# PCB.net
KiCad netlist of a schematic drawn in EAGLE
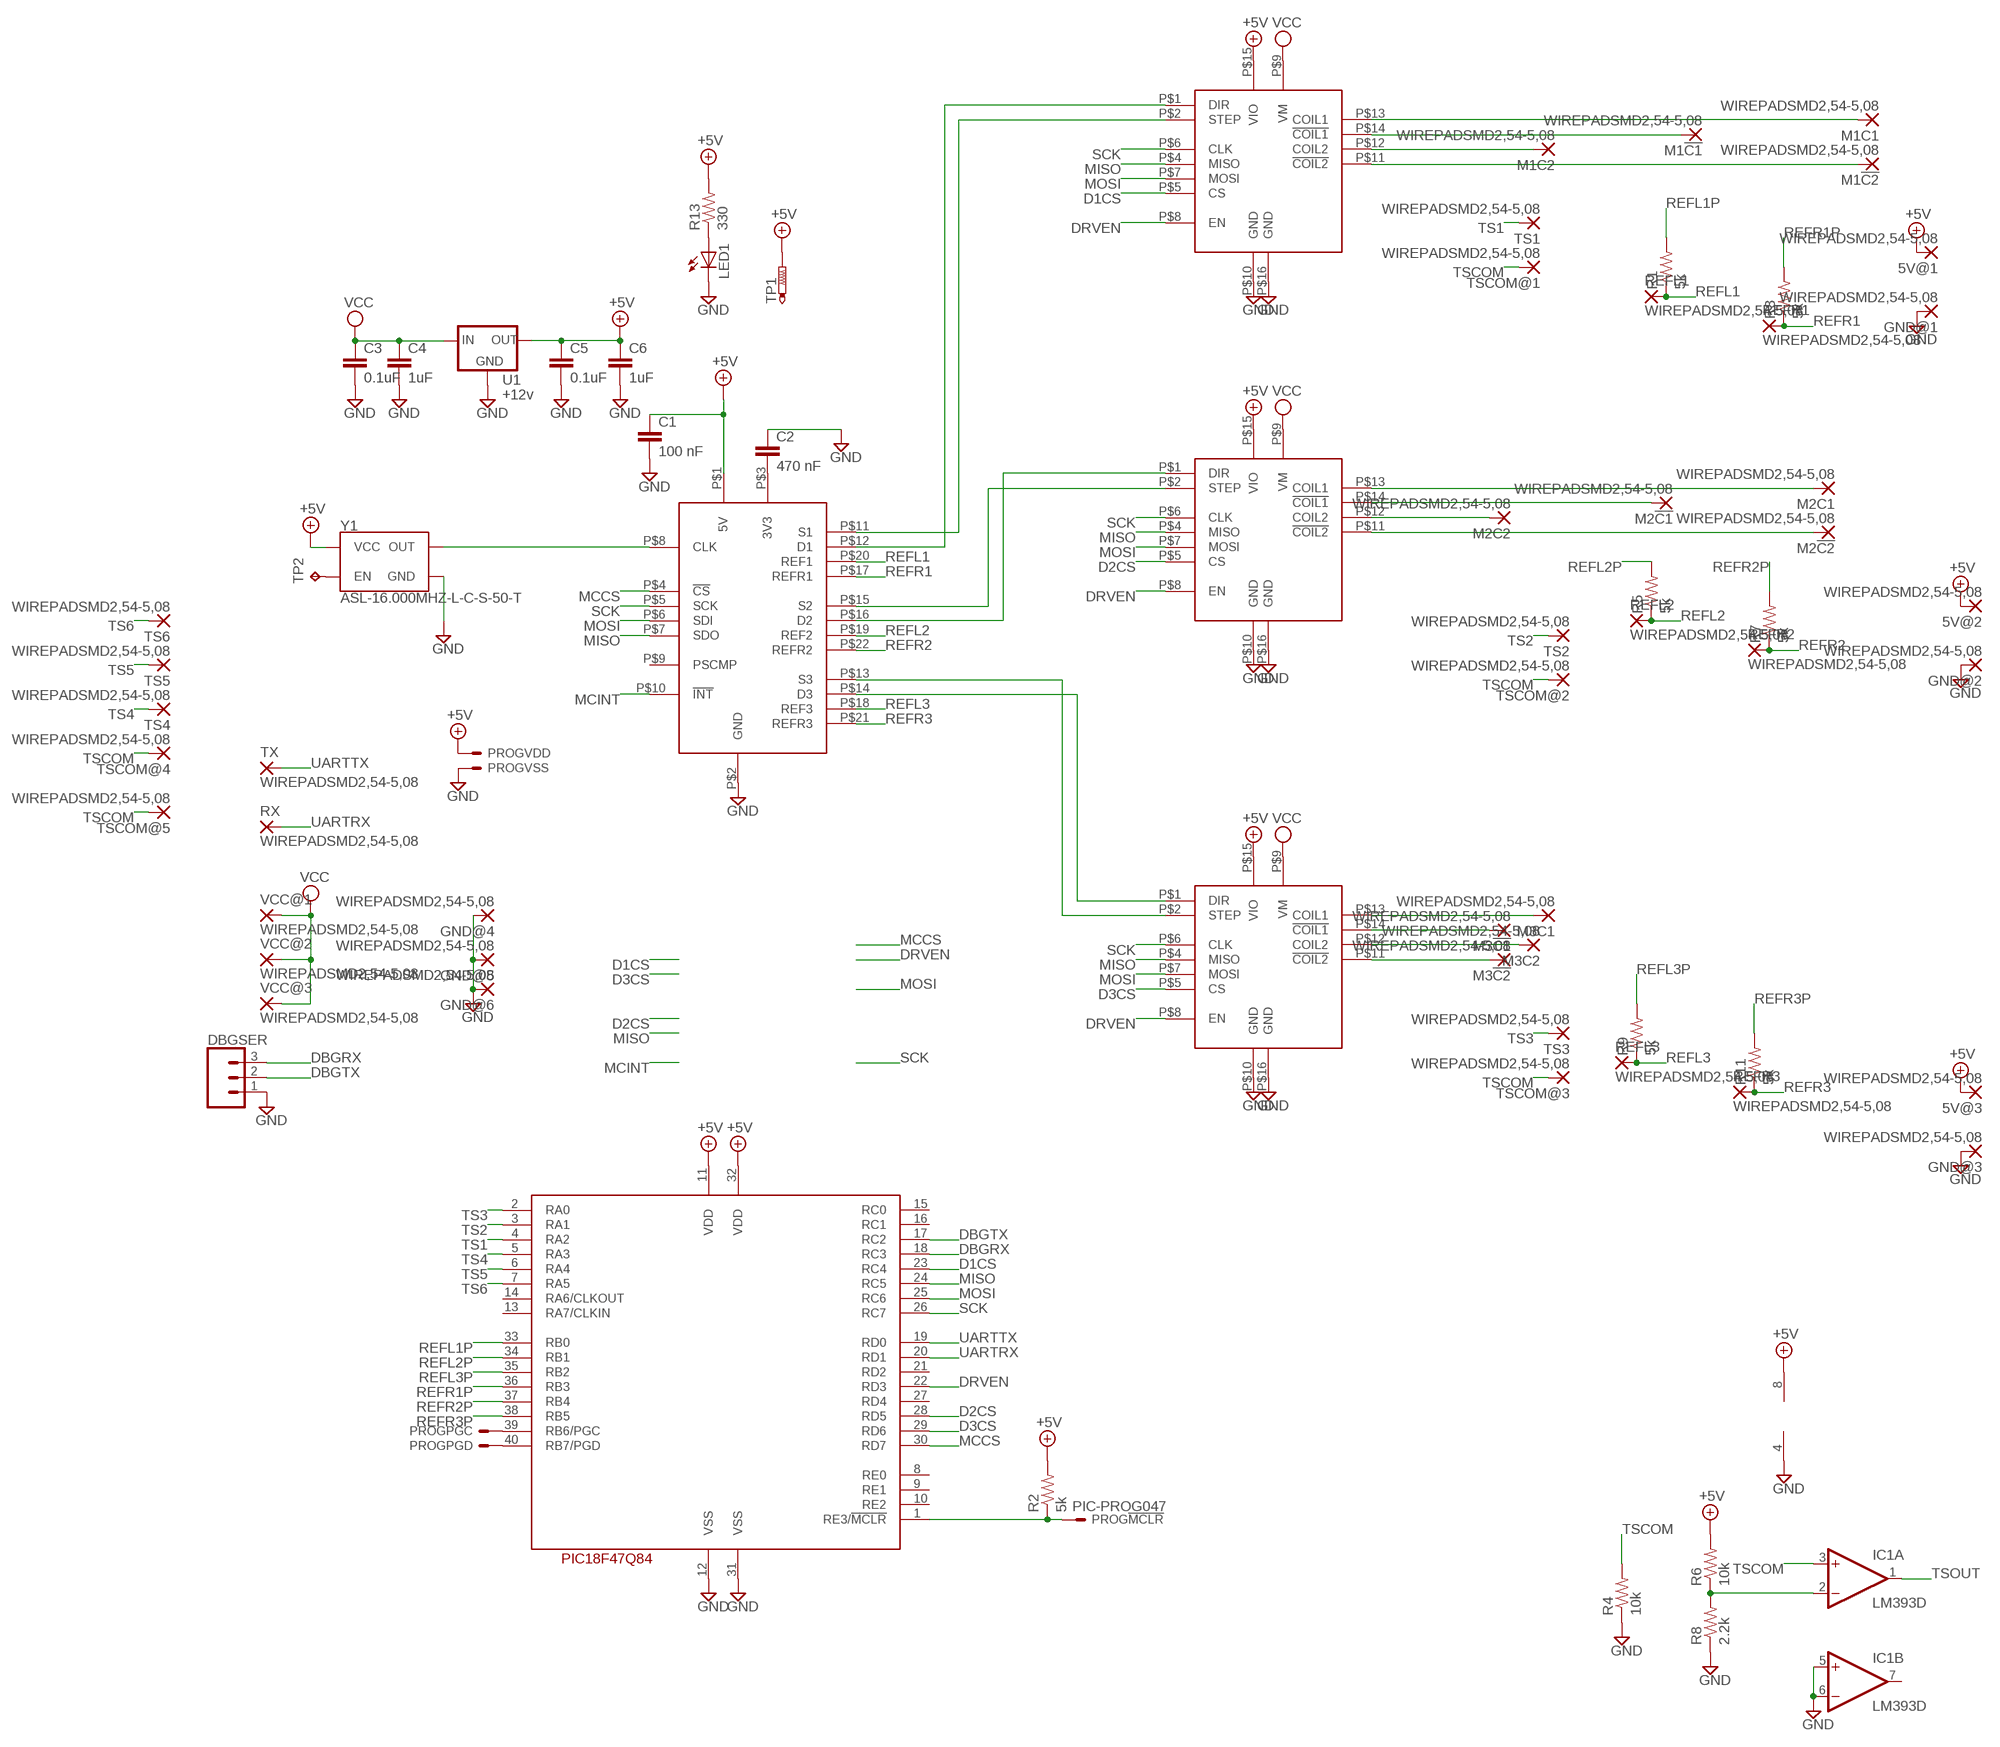
[diagram p0: schematic, sheet 1]

(export (version "E")
  (design (tool "Eeschema 10.0.6"))
  (components
    (comp (ref "5V@1")
      (value "WIREPADSMD2,54-5,08")
      (footprint "eagle-import:SMD2,54-5,08")
      (libsource (lib "eagle-import") (part "WIREPADSMD2,54-5,08"))
    )
    (comp (ref "5V@2")
      (value "WIREPADSMD2,54-5,08")
      (footprint "eagle-import:SMD2,54-5,08")
      (libsource (lib "eagle-import") (part "WIREPADSMD2,54-5,08"))
    )
    (comp (ref "5V@3")
      (value "WIREPADSMD2,54-5,08")
      (footprint "eagle-import:SMD2,54-5,08")
      (libsource (lib "eagle-import") (part "WIREPADSMD2,54-5,08"))
    )
    (comp (ref "C1")
      (value "100 nF")
      (footprint "eagle-import:C1206")
      (libsource (lib "eagle-import") (part "C-EUC1206"))
    )
    (comp (ref "C2")
      (value "470 nF")
      (footprint "eagle-import:C1206")
      (libsource (lib "eagle-import") (part "C-EUC1206"))
    )
    (comp (ref "C3")
      (value "0.1uF")
      (footprint "eagle-import:C1206")
      (libsource (lib "eagle-import") (part "C-EUC1206"))
    )
    (comp (ref "C4")
      (value "1uF")
      (footprint "eagle-import:C1206")
      (libsource (lib "eagle-import") (part "C-EUC1206"))
    )
    (comp (ref "C5")
      (value "0.1uF")
      (footprint "eagle-import:C1206")
      (libsource (lib "eagle-import") (part "C-EUC1206"))
    )
    (comp (ref "C6")
      (value "1uF")
      (footprint "eagle-import:C1206")
      (libsource (lib "eagle-import") (part "C-EUC1206"))
    )
    (comp (ref "DBGSER")
      (value "CONN_03")
      (footprint "eagle-import:1X03")
      (libsource (lib "eagle-import") (part "CONN_03"))
    )
    (comp (ref "DRV1")
      (value "SILENTSTEPSTICK-DIPONLY")
      (footprint "eagle-import:SILENTSTEPSTICK-DIPONLY")
      (libsource (lib "eagle-import") (part "SILENTSTEPSTICK-DIPONLY"))
    )
    (comp (ref "DRV2")
      (value "SILENTSTEPSTICK-DIPONLY")
      (footprint "eagle-import:SILENTSTEPSTICK-DIPONLY")
      (libsource (lib "eagle-import") (part "SILENTSTEPSTICK-DIPONLY"))
    )
    (comp (ref "DRV3")
      (value "SILENTSTEPSTICK-DIPONLY")
      (footprint "eagle-import:SILENTSTEPSTICK-DIPONLY")
      (libsource (lib "eagle-import") (part "SILENTSTEPSTICK-DIPONLY"))
    )
    (comp (ref "GND@1")
      (value "WIREPADSMD2,54-5,08")
      (footprint "eagle-import:SMD2,54-5,08")
      (libsource (lib "eagle-import") (part "WIREPADSMD2,54-5,08"))
    )
    (comp (ref "GND@2")
      (value "WIREPADSMD2,54-5,08")
      (footprint "eagle-import:SMD2,54-5,08")
      (libsource (lib "eagle-import") (part "WIREPADSMD2,54-5,08"))
    )
    (comp (ref "GND@3")
      (value "WIREPADSMD2,54-5,08")
      (footprint "eagle-import:SMD2,54-5,08")
      (libsource (lib "eagle-import") (part "WIREPADSMD2,54-5,08"))
    )
    (comp (ref "GND@4")
      (value "WIREPADSMD2,54-5,08")
      (footprint "eagle-import:SMD2,54-5,08")
      (libsource (lib "eagle-import") (part "WIREPADSMD2,54-5,08"))
    )
    (comp (ref "GND@5")
      (value "WIREPADSMD2,54-5,08")
      (footprint "eagle-import:SMD2,54-5,08")
      (libsource (lib "eagle-import") (part "WIREPADSMD2,54-5,08"))
    )
    (comp (ref "GND@6")
      (value "WIREPADSMD2,54-5,08")
      (footprint "eagle-import:SMD2,54-5,08")
      (libsource (lib "eagle-import") (part "WIREPADSMD2,54-5,08"))
    )
    (comp (ref "IC1")
      (value "LM393D")
      (footprint "eagle-import:SO08")
      (libsource (lib "eagle-import") (part "LM393D"))
    )
    (comp (ref "LED1")
      (value "LEDCHIPLED_1206")
      (footprint "eagle-import:CHIPLED_1206")
      (libsource (lib "eagle-import") (part "LEDCHIPLED_1206"))
    )
    (comp (ref "M1!C1")
      (value "WIREPADSMD2,54-5,08")
      (footprint "eagle-import:SMD2,54-5,08")
      (libsource (lib "eagle-import") (part "WIREPADSMD2,54-5,08"))
    )
    (comp (ref "M1!C2")
      (value "WIREPADSMD2,54-5,08")
      (footprint "eagle-import:SMD2,54-5,08")
      (libsource (lib "eagle-import") (part "WIREPADSMD2,54-5,08"))
    )
    (comp (ref "M1C1")
      (value "WIREPADSMD2,54-5,08")
      (footprint "eagle-import:SMD2,54-5,08")
      (libsource (lib "eagle-import") (part "WIREPADSMD2,54-5,08"))
    )
    (comp (ref "M1C2")
      (value "WIREPADSMD2,54-5,08")
      (footprint "eagle-import:SMD2,54-5,08")
      (libsource (lib "eagle-import") (part "WIREPADSMD2,54-5,08"))
    )
    (comp (ref "M2!C1")
      (value "WIREPADSMD2,54-5,08")
      (footprint "eagle-import:SMD2,54-5,08")
      (libsource (lib "eagle-import") (part "WIREPADSMD2,54-5,08"))
    )
    (comp (ref "M2!C2")
      (value "WIREPADSMD2,54-5,08")
      (footprint "eagle-import:SMD2,54-5,08")
      (libsource (lib "eagle-import") (part "WIREPADSMD2,54-5,08"))
    )
    (comp (ref "M2C1")
      (value "WIREPADSMD2,54-5,08")
      (footprint "eagle-import:SMD2,54-5,08")
      (libsource (lib "eagle-import") (part "WIREPADSMD2,54-5,08"))
    )
    (comp (ref "M2C2")
      (value "WIREPADSMD2,54-5,08")
      (footprint "eagle-import:SMD2,54-5,08")
      (libsource (lib "eagle-import") (part "WIREPADSMD2,54-5,08"))
    )
    (comp (ref "M3!C1")
      (value "WIREPADSMD2,54-5,08")
      (footprint "eagle-import:SMD2,54-5,08")
      (libsource (lib "eagle-import") (part "WIREPADSMD2,54-5,08"))
    )
    (comp (ref "M3!C2")
      (value "WIREPADSMD2,54-5,08")
      (footprint "eagle-import:SMD2,54-5,08")
      (libsource (lib "eagle-import") (part "WIREPADSMD2,54-5,08"))
    )
    (comp (ref "M3C1")
      (value "WIREPADSMD2,54-5,08")
      (footprint "eagle-import:SMD2,54-5,08")
      (libsource (lib "eagle-import") (part "WIREPADSMD2,54-5,08"))
    )
    (comp (ref "M3C2")
      (value "WIREPADSMD2,54-5,08")
      (footprint "eagle-import:SMD2,54-5,08")
      (libsource (lib "eagle-import") (part "WIREPADSMD2,54-5,08"))
    )
    (comp (ref "PROG")
      (value "PIC-PROG047")
      (footprint "eagle-import:53047-05")
      (fields (field (name "MF") "MOLEX") (field (name "MPN") "53047-0510"))
      (libsource (lib "eagle-import") (part "PIC-PROG047"))
    )
    (comp (ref "R1")
      (value "5k")
      (footprint "eagle-import:M1206")
      (libsource (lib "eagle-import") (part "R-US_M1206"))
    )
    (comp (ref "R2")
      (value "5k")
      (footprint "eagle-import:M1206")
      (libsource (lib "eagle-import") (part "R-US_M1206"))
    )
    (comp (ref "R3")
      (value "5k")
      (footprint "eagle-import:M1206")
      (libsource (lib "eagle-import") (part "R-US_M1206"))
    )
    (comp (ref "R4")
      (value "10k")
      (footprint "eagle-import:M1206")
      (libsource (lib "eagle-import") (part "R-US_M1206"))
    )
    (comp (ref "R5")
      (value "5k")
      (footprint "eagle-import:M1206")
      (libsource (lib "eagle-import") (part "R-US_M1206"))
    )
    (comp (ref "R6")
      (value "10k")
      (footprint "eagle-import:M1206")
      (libsource (lib "eagle-import") (part "R-US_M1206"))
    )
    (comp (ref "R7")
      (value "5k")
      (footprint "eagle-import:M1206")
      (libsource (lib "eagle-import") (part "R-US_M1206"))
    )
    (comp (ref "R8")
      (value "2.2k")
      (footprint "eagle-import:M1206")
      (libsource (lib "eagle-import") (part "R-US_M1206"))
    )
    (comp (ref "R9")
      (value "5k")
      (footprint "eagle-import:M1206")
      (libsource (lib "eagle-import") (part "R-US_M1206"))
    )
    (comp (ref "R11")
      (value "5k")
      (footprint "eagle-import:M1206")
      (libsource (lib "eagle-import") (part "R-US_M1206"))
    )
    (comp (ref "R13")
      (value "330")
      (footprint "eagle-import:M1206")
      (libsource (lib "eagle-import") (part "R-US_M1206"))
    )
    (comp (ref "REFL1")
      (value "WIREPADSMD2,54-5,08")
      (footprint "eagle-import:SMD2,54-5,08")
      (libsource (lib "eagle-import") (part "WIREPADSMD2,54-5,08"))
    )
    (comp (ref "REFL2")
      (value "WIREPADSMD2,54-5,08")
      (footprint "eagle-import:SMD2,54-5,08")
      (libsource (lib "eagle-import") (part "WIREPADSMD2,54-5,08"))
    )
    (comp (ref "REFL3")
      (value "WIREPADSMD2,54-5,08")
      (footprint "eagle-import:SMD2,54-5,08")
      (libsource (lib "eagle-import") (part "WIREPADSMD2,54-5,08"))
    )
    (comp (ref "REFR1")
      (value "WIREPADSMD2,54-5,08")
      (footprint "eagle-import:SMD2,54-5,08")
      (libsource (lib "eagle-import") (part "WIREPADSMD2,54-5,08"))
    )
    (comp (ref "REFR2")
      (value "WIREPADSMD2,54-5,08")
      (footprint "eagle-import:SMD2,54-5,08")
      (libsource (lib "eagle-import") (part "WIREPADSMD2,54-5,08"))
    )
    (comp (ref "REFR3")
      (value "WIREPADSMD2,54-5,08")
      (footprint "eagle-import:SMD2,54-5,08")
      (libsource (lib "eagle-import") (part "WIREPADSMD2,54-5,08"))
    )
    (comp (ref "RX")
      (value "WIREPADSMD2,54-5,08")
      (footprint "eagle-import:SMD2,54-5,08")
      (libsource (lib "eagle-import") (part "WIREPADSMD2,54-5,08"))
    )
    (comp (ref "TP1")
      (value "PTR1PAD1-17")
      (footprint "eagle-import:P1-17")
      (libsource (lib "eagle-import") (part "PTR1PAD1-17"))
    )
    (comp (ref "TP2")
      (value "TPB1,27")
      (footprint "eagle-import:B1,27")
      (libsource (lib "eagle-import") (part "TPB1,27"))
    )
    (comp (ref "TS1")
      (value "WIREPADSMD2,54-5,08")
      (footprint "eagle-import:SMD2,54-5,08")
      (libsource (lib "eagle-import") (part "WIREPADSMD2,54-5,08"))
    )
    (comp (ref "TS2")
      (value "WIREPADSMD2,54-5,08")
      (footprint "eagle-import:SMD2,54-5,08")
      (libsource (lib "eagle-import") (part "WIREPADSMD2,54-5,08"))
    )
    (comp (ref "TS3")
      (value "WIREPADSMD2,54-5,08")
      (footprint "eagle-import:SMD2,54-5,08")
      (libsource (lib "eagle-import") (part "WIREPADSMD2,54-5,08"))
    )
    (comp (ref "TS4")
      (value "WIREPADSMD2,54-5,08")
      (footprint "eagle-import:SMD2,54-5,08")
      (libsource (lib "eagle-import") (part "WIREPADSMD2,54-5,08"))
    )
    (comp (ref "TS5")
      (value "WIREPADSMD2,54-5,08")
      (footprint "eagle-import:SMD2,54-5,08")
      (libsource (lib "eagle-import") (part "WIREPADSMD2,54-5,08"))
    )
    (comp (ref "TS6")
      (value "WIREPADSMD2,54-5,08")
      (footprint "eagle-import:SMD2,54-5,08")
      (libsource (lib "eagle-import") (part "WIREPADSMD2,54-5,08"))
    )
    (comp (ref "TSCOM@1")
      (value "WIREPADSMD2,54-5,08")
      (footprint "eagle-import:SMD2,54-5,08")
      (libsource (lib "eagle-import") (part "WIREPADSMD2,54-5,08"))
    )
    (comp (ref "TSCOM@2")
      (value "WIREPADSMD2,54-5,08")
      (footprint "eagle-import:SMD2,54-5,08")
      (libsource (lib "eagle-import") (part "WIREPADSMD2,54-5,08"))
    )
    (comp (ref "TSCOM@3")
      (value "WIREPADSMD2,54-5,08")
      (footprint "eagle-import:SMD2,54-5,08")
      (libsource (lib "eagle-import") (part "WIREPADSMD2,54-5,08"))
    )
    (comp (ref "TSCOM@4")
      (value "WIREPADSMD2,54-5,08")
      (footprint "eagle-import:SMD2,54-5,08")
      (libsource (lib "eagle-import") (part "WIREPADSMD2,54-5,08"))
    )
    (comp (ref "TSCOM@5")
      (value "WIREPADSMD2,54-5,08")
      (footprint "eagle-import:SMD2,54-5,08")
      (libsource (lib "eagle-import") (part "WIREPADSMD2,54-5,08"))
    )
    (comp (ref "TX")
      (value "WIREPADSMD2,54-5,08")
      (footprint "eagle-import:SMD2,54-5,08")
      (libsource (lib "eagle-import") (part "WIREPADSMD2,54-5,08"))
    )
    (comp (ref "U$1")
      (value "TMC429-BOB")
      (footprint "eagle-import:TMC429-BOB")
      (libsource (lib "eagle-import") (part "TMC429-BOB"))
    )
    (comp (ref "U1")
      (value "+12v")
      (footprint "eagle-import:TO-252")
      (libsource (lib "eagle-import") (part "V_REG_78XX7812"))
    )
    (comp (ref "U2")
      (value "PIC18F47Q84")
      (footprint "eagle-import:DIL40")
      (libsource (lib "eagle-import") (part "PIC18F47Q84"))
    )
    (comp (ref "VCC@1")
      (value "WIREPADSMD2,54-5,08")
      (footprint "eagle-import:SMD2,54-5,08")
      (libsource (lib "eagle-import") (part "WIREPADSMD2,54-5,08"))
    )
    (comp (ref "VCC@2")
      (value "WIREPADSMD2,54-5,08")
      (footprint "eagle-import:SMD2,54-5,08")
      (libsource (lib "eagle-import") (part "WIREPADSMD2,54-5,08"))
    )
    (comp (ref "VCC@3")
      (value "WIREPADSMD2,54-5,08")
      (footprint "eagle-import:SMD2,54-5,08")
      (libsource (lib "eagle-import") (part "WIREPADSMD2,54-5,08"))
    )
    (comp (ref "Y1")
      (value "ASL-16.000MHZ-L-C-S-50-T")
      (footprint "eagle-import:OSCILLATOR-SMD-7X5-4PAD")
      (libsource (lib "eagle-import") (part "OSCILLATORSMD-7X5-4PAD"))
    )
  )
  (nets
    (net (code "1") (name "+5V") (class "Default")
      (node (ref "5V@1") (pin "1") (pinfunction "P_1") (pintype "passive"))
      (node (ref "5V@2") (pin "1") (pinfunction "P_1") (pintype "passive"))
      (node (ref "5V@3") (pin "1") (pinfunction "P_1") (pintype "passive"))
      (node (ref "C1") (pin "1") (pinfunction "1_1") (pintype "passive"))
      (node (ref "C5") (pin "1") (pinfunction "1_1") (pintype "passive"))
      (node (ref "C6") (pin "1") (pinfunction "1_1") (pintype "passive"))
      (node (ref "DRV1") (pin "P$15") (pinfunction "VIO_P$15") (pintype "bidirectional"))
      (node (ref "DRV2") (pin "P$15") (pinfunction "VIO_P$15") (pintype "bidirectional"))
      (node (ref "DRV3") (pin "P$15") (pinfunction "VIO_P$15") (pintype "bidirectional"))
      (node (ref "IC1") (pin "8") (pinfunction "V+_8") (pintype "power_in"))
      (node (ref "PROG") (pin "2") (pinfunction "S_2") (pintype "passive"))
      (node (ref "R13") (pin "2") (pinfunction "2_2") (pintype "passive"))
      (node (ref "R2") (pin "2") (pinfunction "2_2") (pintype "passive"))
      (node (ref "R6") (pin "2") (pinfunction "2_2") (pintype "passive"))
      (node (ref "TP1") (pin "TP") (pinfunction "TP_TP") (pintype "input"))
      (node (ref "U$1") (pin "P$1") (pinfunction "5V_P$1") (pintype "bidirectional"))
      (node (ref "U1") (pin "2") (pinfunction "OUT_2") (pintype "passive"))
      (node (ref "U2") (pin "11") (pinfunction "VDD_11") (pintype "bidirectional"))
      (node (ref "U2") (pin "32") (pinfunction "VDD_32") (pintype "bidirectional"))
      (node (ref "Y1") (pin "4") (pinfunction "VCC_4") (pintype "bidirectional"))
    )
    (net (code "2") (name "/D1CS") (class "Default")
      (node (ref "DRV1") (pin "P$5") (pinfunction "CS_P$5") (pintype "bidirectional"))
      (node (ref "U2") (pin "23") (pinfunction "RC4_23") (pintype "bidirectional"))
    )
    (net (code "3") (name "/D2CS") (class "Default")
      (node (ref "DRV2") (pin "P$5") (pinfunction "CS_P$5") (pintype "bidirectional"))
      (node (ref "U2") (pin "28") (pinfunction "RD5_28") (pintype "bidirectional"))
    )
    (net (code "4") (name "/D3CS") (class "Default")
      (node (ref "DRV3") (pin "P$5") (pinfunction "CS_P$5") (pintype "bidirectional"))
      (node (ref "U2") (pin "29") (pinfunction "RD6_29") (pintype "bidirectional"))
    )
    (net (code "5") (name "/DBGRX") (class "Default")
      (node (ref "DBGSER") (pin "3") (pinfunction "3_3") (pintype "passive"))
      (node (ref "U2") (pin "18") (pinfunction "RC3_18") (pintype "bidirectional"))
    )
    (net (code "6") (name "/DBGTX") (class "Default")
      (node (ref "DBGSER") (pin "2") (pinfunction "2_2") (pintype "passive"))
      (node (ref "U2") (pin "17") (pinfunction "RC2_17") (pintype "bidirectional"))
    )
    (net (code "7") (name "/DRVEN") (class "Default")
      (node (ref "DRV1") (pin "P$8") (pinfunction "EN_P$8") (pintype "bidirectional"))
      (node (ref "DRV2") (pin "P$8") (pinfunction "EN_P$8") (pintype "bidirectional"))
      (node (ref "DRV3") (pin "P$8") (pinfunction "EN_P$8") (pintype "bidirectional"))
      (node (ref "U2") (pin "22") (pinfunction "RD3_22") (pintype "bidirectional"))
    )
    (net (code "8") (name "/MCCS") (class "Default")
      (node (ref "U$1") (pin "P$4") (pinfunction "~{CS}_P$4") (pintype "bidirectional"))
      (node (ref "U2") (pin "30") (pinfunction "RD7_30") (pintype "bidirectional"))
    )
    (net (code "9") (name "/MCINT") (class "Default")
      (node (ref "U$1") (pin "P$10") (pinfunction "~{INT}_P$10") (pintype "bidirectional"))
    )
    (net (code "10") (name "/MISO") (class "Default")
      (node (ref "DRV1") (pin "P$4") (pinfunction "MISO_P$4") (pintype "bidirectional"))
      (node (ref "DRV2") (pin "P$4") (pinfunction "MISO_P$4") (pintype "bidirectional"))
      (node (ref "DRV3") (pin "P$4") (pinfunction "MISO_P$4") (pintype "bidirectional"))
      (node (ref "U$1") (pin "P$7") (pinfunction "SDO_P$7") (pintype "bidirectional"))
      (node (ref "U2") (pin "24") (pinfunction "RC5_24") (pintype "bidirectional"))
    )
    (net (code "11") (name "/MOSI") (class "Default")
      (node (ref "DRV1") (pin "P$7") (pinfunction "MOSI_P$7") (pintype "bidirectional"))
      (node (ref "DRV2") (pin "P$7") (pinfunction "MOSI_P$7") (pintype "bidirectional"))
      (node (ref "DRV3") (pin "P$7") (pinfunction "MOSI_P$7") (pintype "bidirectional"))
      (node (ref "U$1") (pin "P$6") (pinfunction "SDI_P$6") (pintype "bidirectional"))
      (node (ref "U2") (pin "25") (pinfunction "RC6_25") (pintype "bidirectional"))
    )
    (net (code "12") (name "/REFL1") (class "Default")
      (node (ref "R1") (pin "1") (pinfunction "1_1") (pintype "passive"))
      (node (ref "REFL1") (pin "1") (pinfunction "P_1") (pintype "passive"))
      (node (ref "U$1") (pin "P$20") (pinfunction "REF1_P$20") (pintype "bidirectional"))
    )
    (net (code "13") (name "/REFL1P") (class "Default")
      (node (ref "R1") (pin "2") (pinfunction "2_2") (pintype "passive"))
      (node (ref "U2") (pin "33") (pinfunction "RB0_33") (pintype "bidirectional"))
    )
    (net (code "14") (name "/REFL2") (class "Default")
      (node (ref "R5") (pin "1") (pinfunction "1_1") (pintype "passive"))
      (node (ref "REFL2") (pin "1") (pinfunction "P_1") (pintype "passive"))
      (node (ref "U$1") (pin "P$19") (pinfunction "REF2_P$19") (pintype "bidirectional"))
    )
    (net (code "15") (name "/REFL2P") (class "Default")
      (node (ref "R5") (pin "2") (pinfunction "2_2") (pintype "passive"))
      (node (ref "U2") (pin "34") (pinfunction "RB1_34") (pintype "bidirectional"))
    )
    (net (code "16") (name "/REFL3") (class "Default")
      (node (ref "R9") (pin "1") (pinfunction "1_1") (pintype "passive"))
      (node (ref "REFL3") (pin "1") (pinfunction "P_1") (pintype "passive"))
      (node (ref "U$1") (pin "P$18") (pinfunction "REF3_P$18") (pintype "bidirectional"))
    )
    (net (code "17") (name "/REFL3P") (class "Default")
      (node (ref "R9") (pin "2") (pinfunction "2_2") (pintype "passive"))
      (node (ref "U2") (pin "35") (pinfunction "RB2_35") (pintype "bidirectional"))
    )
    (net (code "18") (name "/REFR1") (class "Default")
      (node (ref "R3") (pin "1") (pinfunction "1_1") (pintype "passive"))
      (node (ref "REFR1") (pin "1") (pinfunction "P_1") (pintype "passive"))
      (node (ref "U$1") (pin "P$17") (pinfunction "REFR1_P$17") (pintype "bidirectional"))
    )
    (net (code "19") (name "/REFR1P") (class "Default")
      (node (ref "R3") (pin "2") (pinfunction "2_2") (pintype "passive"))
      (node (ref "U2") (pin "36") (pinfunction "RB3_36") (pintype "bidirectional"))
    )
    (net (code "20") (name "/REFR2") (class "Default")
      (node (ref "R7") (pin "1") (pinfunction "1_1") (pintype "passive"))
      (node (ref "REFR2") (pin "1") (pinfunction "P_1") (pintype "passive"))
      (node (ref "U$1") (pin "P$22") (pinfunction "REFR2_P$22") (pintype "bidirectional"))
    )
    (net (code "21") (name "/REFR2P") (class "Default")
      (node (ref "R7") (pin "2") (pinfunction "2_2") (pintype "passive"))
      (node (ref "U2") (pin "37") (pinfunction "RB4_37") (pintype "bidirectional"))
    )
    (net (code "22") (name "/REFR3") (class "Default")
      (node (ref "R11") (pin "1") (pinfunction "1_1") (pintype "passive"))
      (node (ref "REFR3") (pin "1") (pinfunction "P_1") (pintype "passive"))
      (node (ref "U$1") (pin "P$21") (pinfunction "REFR3_P$21") (pintype "bidirectional"))
    )
    (net (code "23") (name "/REFR3P") (class "Default")
      (node (ref "R11") (pin "2") (pinfunction "2_2") (pintype "passive"))
      (node (ref "U2") (pin "38") (pinfunction "RB5_38") (pintype "bidirectional"))
    )
    (net (code "24") (name "/SCK") (class "Default")
      (node (ref "DRV1") (pin "P$6") (pinfunction "CLK_P$6") (pintype "bidirectional"))
      (node (ref "DRV2") (pin "P$6") (pinfunction "CLK_P$6") (pintype "bidirectional"))
      (node (ref "DRV3") (pin "P$6") (pinfunction "CLK_P$6") (pintype "bidirectional"))
      (node (ref "U$1") (pin "P$5") (pinfunction "SCK_P$5") (pintype "bidirectional"))
      (node (ref "U2") (pin "26") (pinfunction "RC7_26") (pintype "bidirectional"))
    )
    (net (code "25") (name "/TS1") (class "Default")
      (node (ref "TS1") (pin "1") (pinfunction "P_1") (pintype "passive"))
      (node (ref "U2") (pin "4") (pinfunction "RA2_4") (pintype "bidirectional"))
    )
    (net (code "26") (name "/TS2") (class "Default")
      (node (ref "TS2") (pin "1") (pinfunction "P_1") (pintype "passive"))
      (node (ref "U2") (pin "3") (pinfunction "RA1_3") (pintype "bidirectional"))
    )
    (net (code "27") (name "/TS3") (class "Default")
      (node (ref "TS3") (pin "1") (pinfunction "P_1") (pintype "passive"))
      (node (ref "U2") (pin "2") (pinfunction "RA0_2") (pintype "bidirectional"))
    )
    (net (code "28") (name "/TS4") (class "Default")
      (node (ref "TS4") (pin "1") (pinfunction "P_1") (pintype "passive"))
      (node (ref "U2") (pin "5") (pinfunction "RA3_5") (pintype "bidirectional"))
    )
    (net (code "29") (name "/TS5") (class "Default")
      (node (ref "TS5") (pin "1") (pinfunction "P_1") (pintype "passive"))
      (node (ref "U2") (pin "6") (pinfunction "RA4_6") (pintype "bidirectional"))
    )
    (net (code "30") (name "/TS6") (class "Default")
      (node (ref "TS6") (pin "1") (pinfunction "P_1") (pintype "passive"))
      (node (ref "U2") (pin "7") (pinfunction "RA5_7") (pintype "bidirectional"))
    )
    (net (code "31") (name "/TSCOM") (class "Default")
      (node (ref "IC1") (pin "3") (pinfunction "+IN_3") (pintype "input"))
      (node (ref "R4") (pin "2") (pinfunction "2_2") (pintype "passive"))
      (node (ref "TSCOM@1") (pin "1") (pinfunction "P_1") (pintype "passive"))
      (node (ref "TSCOM@2") (pin "1") (pinfunction "P_1") (pintype "passive"))
      (node (ref "TSCOM@3") (pin "1") (pinfunction "P_1") (pintype "passive"))
      (node (ref "TSCOM@4") (pin "1") (pinfunction "P_1") (pintype "passive"))
      (node (ref "TSCOM@5") (pin "1") (pinfunction "P_1") (pintype "passive"))
    )
    (net (code "32") (name "/TSOUT") (class "Default")
      (node (ref "IC1") (pin "1") (pinfunction "OUT_1") (pintype "output"))
    )
    (net (code "33") (name "/UARTRX") (class "Default")
      (node (ref "RX") (pin "1") (pinfunction "P_1") (pintype "passive"))
      (node (ref "U2") (pin "20") (pinfunction "RD1_20") (pintype "bidirectional"))
    )
    (net (code "34") (name "/UARTTX") (class "Default")
      (node (ref "TX") (pin "1") (pinfunction "P_1") (pintype "passive"))
      (node (ref "U2") (pin "19") (pinfunction "RD0_19") (pintype "bidirectional"))
    )
    (net (code "35") (name "GND") (class "Default")
      (node (ref "C1") (pin "2") (pinfunction "2_2") (pintype "passive"))
      (node (ref "C2") (pin "1") (pinfunction "1_1") (pintype "passive"))
      (node (ref "C3") (pin "2") (pinfunction "2_2") (pintype "passive"))
      (node (ref "C4") (pin "2") (pinfunction "2_2") (pintype "passive"))
      (node (ref "C5") (pin "2") (pinfunction "2_2") (pintype "passive"))
      (node (ref "C6") (pin "2") (pinfunction "2_2") (pintype "passive"))
      (node (ref "DBGSER") (pin "1") (pinfunction "1_1") (pintype "passive"))
      (node (ref "DRV1") (pin "P$10") (pinfunction "GND_P$10") (pintype "bidirectional"))
      (node (ref "DRV1") (pin "P$16") (pinfunction "GND_P$16") (pintype "bidirectional"))
      (node (ref "DRV2") (pin "P$10") (pinfunction "GND_P$10") (pintype "bidirectional"))
      (node (ref "DRV2") (pin "P$16") (pinfunction "GND_P$16") (pintype "bidirectional"))
      (node (ref "DRV3") (pin "P$10") (pinfunction "GND_P$10") (pintype "bidirectional"))
      (node (ref "DRV3") (pin "P$16") (pinfunction "GND_P$16") (pintype "bidirectional"))
      (node (ref "GND@1") (pin "1") (pinfunction "P_1") (pintype "passive"))
      (node (ref "GND@2") (pin "1") (pinfunction "P_1") (pintype "passive"))
      (node (ref "GND@3") (pin "1") (pinfunction "P_1") (pintype "passive"))
      (node (ref "GND@4") (pin "1") (pinfunction "P_1") (pintype "passive"))
      (node (ref "GND@5") (pin "1") (pinfunction "P_1") (pintype "passive"))
      (node (ref "GND@6") (pin "1") (pinfunction "P_1") (pintype "passive"))
      (node (ref "IC1") (pin "4") (pinfunction "V-_4") (pintype "power_in"))
      (node (ref "IC1") (pin "5") (pinfunction "+IN_5") (pintype "input"))
      (node (ref "IC1") (pin "6") (pinfunction "-IN_6") (pintype "input"))
      (node (ref "LED1") (pin "C") (pinfunction "C_C") (pintype "passive"))
      (node (ref "PROG") (pin "3") (pinfunction "S_3") (pintype "passive"))
      (node (ref "R4") (pin "1") (pinfunction "1_1") (pintype "passive"))
      (node (ref "R8") (pin "1") (pinfunction "1_1") (pintype "passive"))
      (node (ref "U$1") (pin "P$2") (pinfunction "GND_P$2") (pintype "bidirectional"))
      (node (ref "U1") (pin "3") (pinfunction "GND_3") (pintype "input"))
      (node (ref "U2") (pin "12") (pinfunction "VSS_12") (pintype "bidirectional"))
      (node (ref "U2") (pin "31") (pinfunction "VSS_31") (pintype "bidirectional"))
      (node (ref "Y1") (pin "2") (pinfunction "GND_2") (pintype "bidirectional"))
    )
    (net (code "36") (name "Net-(DRV1-COIL1)") (class "Default")
      (node (ref "DRV1") (pin "P$13") (pinfunction "COIL1_P$13") (pintype "bidirectional"))
      (node (ref "M1C1") (pin "1") (pinfunction "P_1") (pintype "passive"))
    )
    (net (code "37") (name "Net-(DRV1-COIL2)") (class "Default")
      (node (ref "DRV1") (pin "P$12") (pinfunction "COIL2_P$12") (pintype "bidirectional"))
      (node (ref "M1C2") (pin "1") (pinfunction "P_1") (pintype "passive"))
    )
    (net (code "38") (name "Net-(DRV1-DIR)") (class "Default")
      (node (ref "DRV1") (pin "P$1") (pinfunction "DIR_P$1") (pintype "bidirectional"))
      (node (ref "U$1") (pin "P$12") (pinfunction "D1_P$12") (pintype "bidirectional"))
    )
    (net (code "39") (name "Net-(DRV1-STEP)") (class "Default")
      (node (ref "DRV1") (pin "P$2") (pinfunction "STEP_P$2") (pintype "bidirectional"))
      (node (ref "U$1") (pin "P$11") (pinfunction "S1_P$11") (pintype "bidirectional"))
    )
    (net (code "40") (name "Net-(DRV1-~{COIL1})") (class "Default")
      (node (ref "DRV1") (pin "P$14") (pinfunction "~{COIL1}_P$14") (pintype "bidirectional"))
      (node (ref "M1!C1") (pin "1") (pinfunction "P_1") (pintype "passive"))
    )
    (net (code "41") (name "Net-(DRV1-~{COIL2})") (class "Default")
      (node (ref "DRV1") (pin "P$11") (pinfunction "~{COIL2}_P$11") (pintype "bidirectional"))
      (node (ref "M1!C2") (pin "1") (pinfunction "P_1") (pintype "passive"))
    )
    (net (code "42") (name "Net-(DRV2-COIL1)") (class "Default")
      (node (ref "DRV2") (pin "P$13") (pinfunction "COIL1_P$13") (pintype "bidirectional"))
      (node (ref "M2C1") (pin "1") (pinfunction "P_1") (pintype "passive"))
    )
    (net (code "43") (name "Net-(DRV2-COIL2)") (class "Default")
      (node (ref "DRV2") (pin "P$12") (pinfunction "COIL2_P$12") (pintype "bidirectional"))
      (node (ref "M2C2") (pin "1") (pinfunction "P_1") (pintype "passive"))
    )
    (net (code "44") (name "Net-(DRV2-DIR)") (class "Default")
      (node (ref "DRV2") (pin "P$1") (pinfunction "DIR_P$1") (pintype "bidirectional"))
      (node (ref "U$1") (pin "P$16") (pinfunction "D2_P$16") (pintype "bidirectional"))
    )
    (net (code "45") (name "Net-(DRV2-STEP)") (class "Default")
      (node (ref "DRV2") (pin "P$2") (pinfunction "STEP_P$2") (pintype "bidirectional"))
      (node (ref "U$1") (pin "P$15") (pinfunction "S2_P$15") (pintype "bidirectional"))
    )
    (net (code "46") (name "Net-(DRV2-~{COIL1})") (class "Default")
      (node (ref "DRV2") (pin "P$14") (pinfunction "~{COIL1}_P$14") (pintype "bidirectional"))
      (node (ref "M2!C1") (pin "1") (pinfunction "P_1") (pintype "passive"))
    )
    (net (code "47") (name "Net-(DRV2-~{COIL2})") (class "Default")
      (node (ref "DRV2") (pin "P$11") (pinfunction "~{COIL2}_P$11") (pintype "bidirectional"))
      (node (ref "M2!C2") (pin "1") (pinfunction "P_1") (pintype "passive"))
    )
    (net (code "48") (name "Net-(DRV3-COIL1)") (class "Default")
      (node (ref "DRV3") (pin "P$13") (pinfunction "COIL1_P$13") (pintype "bidirectional"))
      (node (ref "M3C1") (pin "1") (pinfunction "P_1") (pintype "passive"))
    )
    (net (code "49") (name "Net-(DRV3-COIL2)") (class "Default")
      (node (ref "DRV3") (pin "P$12") (pinfunction "COIL2_P$12") (pintype "bidirectional"))
      (node (ref "M3C2") (pin "1") (pinfunction "P_1") (pintype "passive"))
    )
    (net (code "50") (name "Net-(DRV3-DIR)") (class "Default")
      (node (ref "DRV3") (pin "P$1") (pinfunction "DIR_P$1") (pintype "bidirectional"))
      (node (ref "U$1") (pin "P$14") (pinfunction "D3_P$14") (pintype "bidirectional"))
    )
    (net (code "51") (name "Net-(DRV3-STEP)") (class "Default")
      (node (ref "DRV3") (pin "P$2") (pinfunction "STEP_P$2") (pintype "bidirectional"))
      (node (ref "U$1") (pin "P$13") (pinfunction "S3_P$13") (pintype "bidirectional"))
    )
    (net (code "52") (name "Net-(DRV3-~{COIL1})") (class "Default")
      (node (ref "DRV3") (pin "P$14") (pinfunction "~{COIL1}_P$14") (pintype "bidirectional"))
      (node (ref "M3!C1") (pin "1") (pinfunction "P_1") (pintype "passive"))
    )
    (net (code "53") (name "Net-(DRV3-~{COIL2})") (class "Default")
      (node (ref "DRV3") (pin "P$11") (pinfunction "~{COIL2}_P$11") (pintype "bidirectional"))
      (node (ref "M3!C2") (pin "1") (pinfunction "P_1") (pintype "passive"))
    )
    (net (code "54") (name "Net-(IC1A--IN)") (class "Default")
      (node (ref "IC1") (pin "2") (pinfunction "-IN_2") (pintype "input"))
      (node (ref "R6") (pin "1") (pinfunction "1_1") (pintype "passive"))
      (node (ref "R8") (pin "2") (pinfunction "2_2") (pintype "passive"))
    )
    (net (code "55") (name "Net-(LED1-PadA)") (class "Default")
      (node (ref "LED1") (pin "A") (pinfunction "A_A") (pintype "passive"))
      (node (ref "R13") (pin "1") (pinfunction "1_1") (pintype "passive"))
    )
    (net (code "56") (name "Net-(PROGA-S)") (class "Default")
      (node (ref "PROG") (pin "1") (pinfunction "S_1") (pintype "passive"))
      (node (ref "R2") (pin "1") (pinfunction "1_1") (pintype "passive"))
      (node (ref "U2") (pin "1") (pinfunction "RE3/~{MCLR}_1") (pintype "bidirectional"))
    )
    (net (code "57") (name "Net-(PROGB-S)") (class "Default")
      (node (ref "PROG") (pin "5") (pinfunction "S_5") (pintype "passive"))
      (node (ref "U2") (pin "39") (pinfunction "RB6/PGC_39") (pintype "bidirectional"))
    )
    (net (code "58") (name "Net-(PROGC-S)") (class "Default")
      (node (ref "PROG") (pin "4") (pinfunction "S_4") (pintype "passive"))
      (node (ref "U2") (pin "40") (pinfunction "RB7/PGD_40") (pintype "bidirectional"))
    )
    (net (code "59") (name "Net-(U$1-3V3)") (class "Default")
      (node (ref "C2") (pin "2") (pinfunction "2_2") (pintype "passive"))
      (node (ref "U$1") (pin "P$3") (pinfunction "3V3_P$3") (pintype "bidirectional"))
    )
    (net (code "60") (name "Net-(U$1-CLK)") (class "Default")
      (node (ref "U$1") (pin "P$8") (pinfunction "CLK_P$8") (pintype "bidirectional"))
      (node (ref "Y1") (pin "3") (pinfunction "OUT_3") (pintype "bidirectional"))
    )
    (net (code "61") (name "Net-(Y1-EN)") (class "Default")
      (node (ref "TP2") (pin "TP") (pinfunction "TP_TP") (pintype "input"))
      (node (ref "Y1") (pin "1") (pinfunction "EN_1") (pintype "bidirectional"))
    )
    (net (code "62") (name "VCC") (class "Default")
      (node (ref "C3") (pin "1") (pinfunction "1_1") (pintype "passive"))
      (node (ref "C4") (pin "1") (pinfunction "1_1") (pintype "passive"))
      (node (ref "DRV1") (pin "P$9") (pinfunction "VM_P$9") (pintype "bidirectional"))
      (node (ref "DRV2") (pin "P$9") (pinfunction "VM_P$9") (pintype "bidirectional"))
      (node (ref "DRV3") (pin "P$9") (pinfunction "VM_P$9") (pintype "bidirectional"))
      (node (ref "U1") (pin "1") (pinfunction "IN_1") (pintype "input"))
      (node (ref "VCC@1") (pin "1") (pinfunction "P_1") (pintype "passive"))
      (node (ref "VCC@2") (pin "1") (pinfunction "P_1") (pintype "passive"))
      (node (ref "VCC@3") (pin "1") (pinfunction "P_1") (pintype "passive"))
    )
    (net (code "63") (name "unconnected-(IC1B-OUT-Pad7)") (class "Default")
      (node (ref "IC1") (pin "7") (pinfunction "OUT_7") (pintype "output"))
    )
    (net (code "64") (name "unconnected-(U$1-PSCMP-PadP$9)") (class "Default")
      (node (ref "U$1") (pin "P$9") (pinfunction "PSCMP_P$9") (pintype "bidirectional"))
    )
    (net (code "65") (name "unconnected-(U2-RA6{slash}CLKOUT-Pad14)") (class "Default")
      (node (ref "U2") (pin "14") (pinfunction "RA6/CLKOUT_14") (pintype "bidirectional"))
    )
    (net (code "66") (name "unconnected-(U2-RA7{slash}CLKIN-Pad13)") (class "Default")
      (node (ref "U2") (pin "13") (pinfunction "RA7/CLKIN_13") (pintype "bidirectional"))
    )
    (net (code "67") (name "unconnected-(U2-RC0-Pad15)") (class "Default")
      (node (ref "U2") (pin "15") (pinfunction "RC0_15") (pintype "bidirectional"))
    )
    (net (code "68") (name "unconnected-(U2-RC1-Pad16)") (class "Default")
      (node (ref "U2") (pin "16") (pinfunction "RC1_16") (pintype "bidirectional"))
    )
    (net (code "69") (name "unconnected-(U2-RD2-Pad21)") (class "Default")
      (node (ref "U2") (pin "21") (pinfunction "RD2_21") (pintype "bidirectional"))
    )
    (net (code "70") (name "unconnected-(U2-RD4-Pad27)") (class "Default")
      (node (ref "U2") (pin "27") (pinfunction "RD4_27") (pintype "bidirectional"))
    )
    (net (code "71") (name "unconnected-(U2-RE0-Pad8)") (class "Default")
      (node (ref "U2") (pin "8") (pinfunction "RE0_8") (pintype "bidirectional"))
    )
    (net (code "72") (name "unconnected-(U2-RE1-Pad9)") (class "Default")
      (node (ref "U2") (pin "9") (pinfunction "RE1_9") (pintype "bidirectional"))
    )
    (net (code "73") (name "unconnected-(U2-RE2-Pad10)") (class "Default")
      (node (ref "U2") (pin "10") (pinfunction "RE2_10") (pintype "bidirectional"))
    )
  )
)
